# esp8266-DS18B20.net
KiCad netlist of a schematic drawn in EAGLE
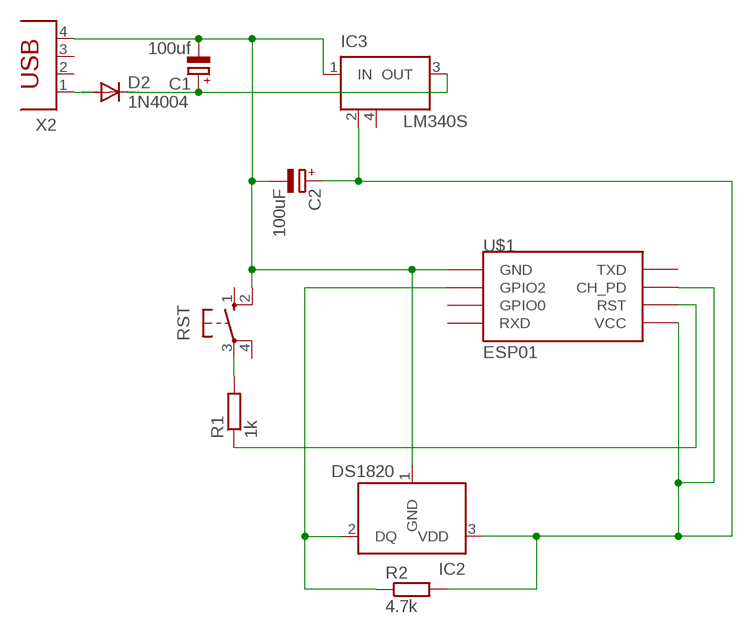
[diagram p0: schematic, sheet 1]

(export (version "E")
  (design (tool "Eeschema 10.0.6"))
  (components
    (comp (ref "C1")
      (value "100uf")
      (footprint "eagle-import:E2,5-5")
      (libsource (lib "eagle-import") (part "CPOL-EUE2.5-5"))
    )
    (comp (ref "C2")
      (value "100uF")
      (footprint "eagle-import:E2,5-5")
      (libsource (lib "eagle-import") (part "CPOL-EUE2.5-5"))
    )
    (comp (ref "D2")
      (value "1N4004")
      (footprint "eagle-import:DO41-10")
      (libsource (lib "eagle-import") (part "1N4004"))
    )
    (comp (ref "IC2")
      (value "DS1820")
      (footprint "eagle-import:TO-92")
      (libsource (lib "eagle-import") (part "DS1820"))
    )
    (comp (ref "IC3")
      (value "LM340S")
      (footprint "eagle-import:SOT223")
      (libsource (lib "eagle-import") (part "LM340S"))
    )
    (comp (ref "R1")
      (value "1k")
      (footprint "eagle-import:0207_12")
      (libsource (lib "eagle-import") (part "R-EU_0207/12"))
    )
    (comp (ref "R2")
      (value "4.7k")
      (footprint "eagle-import:0207_12")
      (libsource (lib "eagle-import") (part "R-EU_0207/12"))
    )
    (comp (ref "RST")
      (value "10-XX")
      (footprint "eagle-import:B3F-10XX")
      (fields (field (name "MPN") "B3F-1000"))
      (libsource (lib "eagle-import") (part "10-XX"))
    )
    (comp (ref "U$1")
      (value "ESP01")
      (footprint "eagle-import:ESP01")
      (libsource (lib "eagle-import") (part "ESP01"))
    )
    (comp (ref "X2")
      (value "PN61729")
      (footprint "eagle-import:PN61729")
      (libsource (lib "eagle-import") (part "PN61729"))
    )
  )
  (nets
    (net (code "1") (name "/5V") (class "Default")
      (node (ref "C1") (pin "+") (pinfunction "+_+") (pintype "passive"))
      (node (ref "D2") (pin "A") (pinfunction "A_A") (pintype "passive"))
      (node (ref "D2") (pin "C") (pinfunction "C_C") (pintype "passive"))
      (node (ref "IC3") (pin "3") (pinfunction "OUT_3") (pintype "passive"))
      (node (ref "X2") (pin "1") (pinfunction "1_1") (pintype "passive"))
    )
    (net (code "2") (name "/GND") (class "Default")
      (node (ref "IC3") (pin "4") (pinfunction "GND_4") (pintype "power_in"))
    )
    (net (code "3") (name "Net-(IC2-DQ)") (class "Default")
      (node (ref "IC2") (pin "2") (pinfunction "DQ_2") (pintype "output"))
      (node (ref "R2") (pin "1") (pinfunction "1_1") (pintype "passive"))
      (node (ref "U$1") (pin "GPIO2") (pinfunction "GPIO2_GPIO2") (pintype "bidirectional"))
    )
    (net (code "4") (name "Net-(IC2-GND)") (class "Default")
      (node (ref "C1") (pin "-") (pinfunction "-_-") (pintype "passive"))
      (node (ref "C2") (pin "-") (pinfunction "-_-") (pintype "passive"))
      (node (ref "IC2") (pin "1") (pinfunction "GND_1") (pintype "power_in"))
      (node (ref "IC3") (pin "1") (pinfunction "IN_1") (pintype "input"))
      (node (ref "RST") (pin "2") (pinfunction "S1_2") (pintype "passive"))
      (node (ref "U$1") (pin "GND") (pinfunction "GND_GND") (pintype "bidirectional"))
      (node (ref "X2") (pin "4") (pinfunction "4_4") (pintype "passive"))
    )
    (net (code "5") (name "Net-(IC2-VDD)") (class "Default")
      (node (ref "C2") (pin "+") (pinfunction "+_+") (pintype "passive"))
      (node (ref "IC2") (pin "3") (pinfunction "VDD_3") (pintype "input"))
      (node (ref "IC3") (pin "2") (pinfunction "GND_2") (pintype "power_in"))
      (node (ref "R2") (pin "2") (pinfunction "2_2") (pintype "passive"))
      (node (ref "U$1") (pin "CH_PD") (pinfunction "CH_PD_CH_PD") (pintype "bidirectional"))
      (node (ref "U$1") (pin "VCC") (pinfunction "VCC_VCC") (pintype "bidirectional"))
    )
    (net (code "6") (name "Net-(R1-Pad1)") (class "Default")
      (node (ref "R1") (pin "1") (pinfunction "1_1") (pintype "passive"))
      (node (ref "U$1") (pin "RST") (pinfunction "RST_RST") (pintype "bidirectional"))
    )
    (net (code "7") (name "Net-(RST-P)") (class "Default")
      (node (ref "R1") (pin "2") (pinfunction "2_2") (pintype "passive"))
      (node (ref "RST") (pin "3") (pinfunction "P_3") (pintype "passive"))
    )
    (net (code "8") (name "unconnected-(RST-P1-Pad4)") (class "Default")
      (node (ref "RST") (pin "4") (pinfunction "P1_4") (pintype "passive"))
    )
    (net (code "9") (name "unconnected-(RST-S-Pad1)") (class "Default")
      (node (ref "RST") (pin "1") (pinfunction "S_1") (pintype "passive"))
    )
    (net (code "10") (name "unconnected-(U$1-PadGPIO0)") (class "Default")
      (node (ref "U$1") (pin "GPIO0") (pinfunction "GPIO0_GPIO0") (pintype "bidirectional"))
    )
    (net (code "11") (name "unconnected-(U$1-RXD-PadRX)") (class "Default")
      (node (ref "U$1") (pin "RX") (pinfunction "RXD_RX") (pintype "bidirectional"))
    )
    (net (code "12") (name "unconnected-(U$1-TXD-PadTX)") (class "Default")
      (node (ref "U$1") (pin "TX") (pinfunction "TXD_TX") (pintype "bidirectional"))
    )
    (net (code "13") (name "unconnected-(X2-Pad2)") (class "Default")
      (node (ref "X2") (pin "2") (pinfunction "2_2") (pintype "passive"))
    )
    (net (code "14") (name "unconnected-(X2-Pad3)") (class "Default")
      (node (ref "X2") (pin "3") (pinfunction "3_3") (pintype "passive"))
    )
  )
)
